# schematic.net
KiCad netlist of a schematic drawn in EAGLE
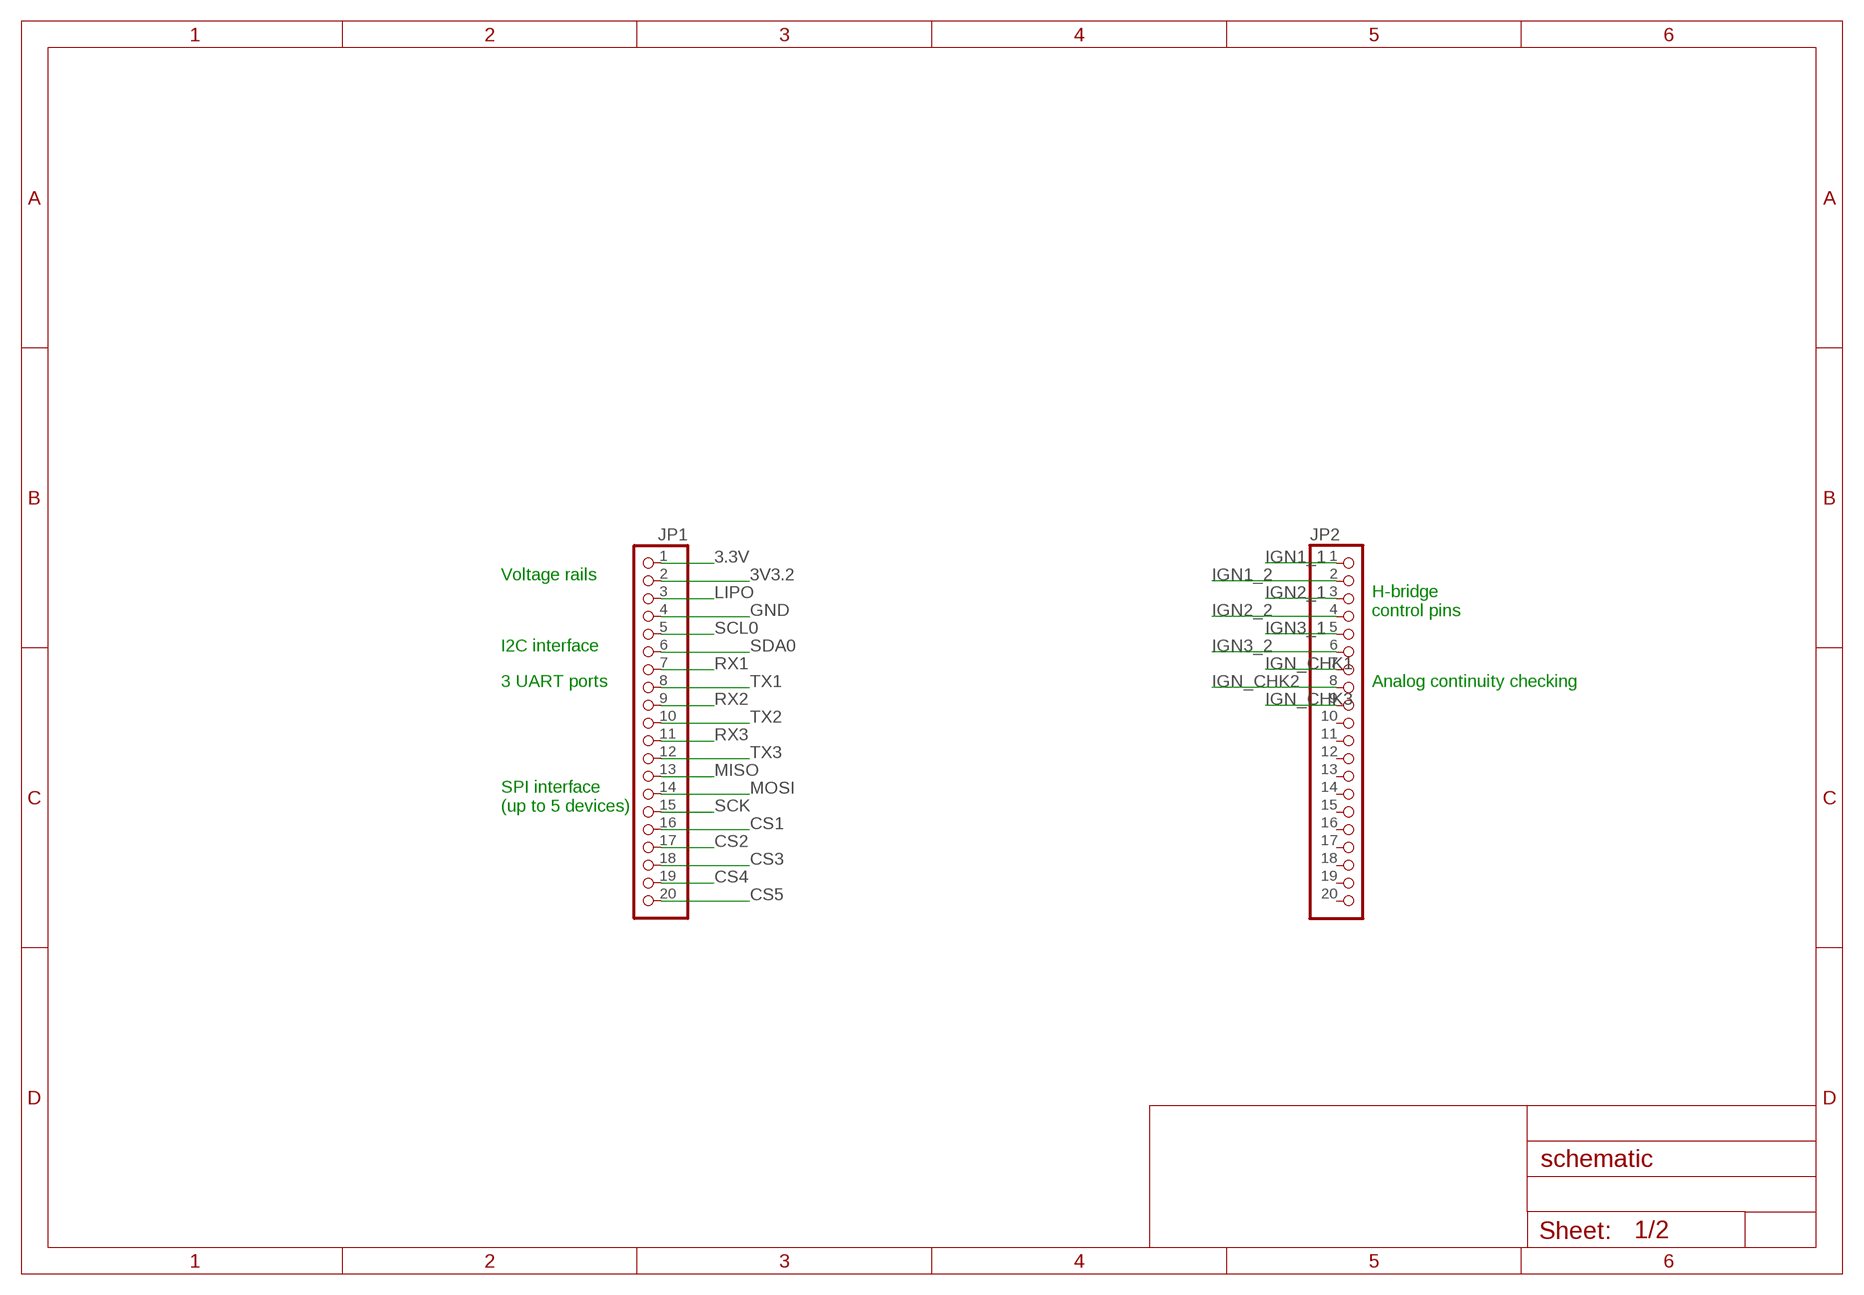
[diagram p0: schematic, sheet 1]
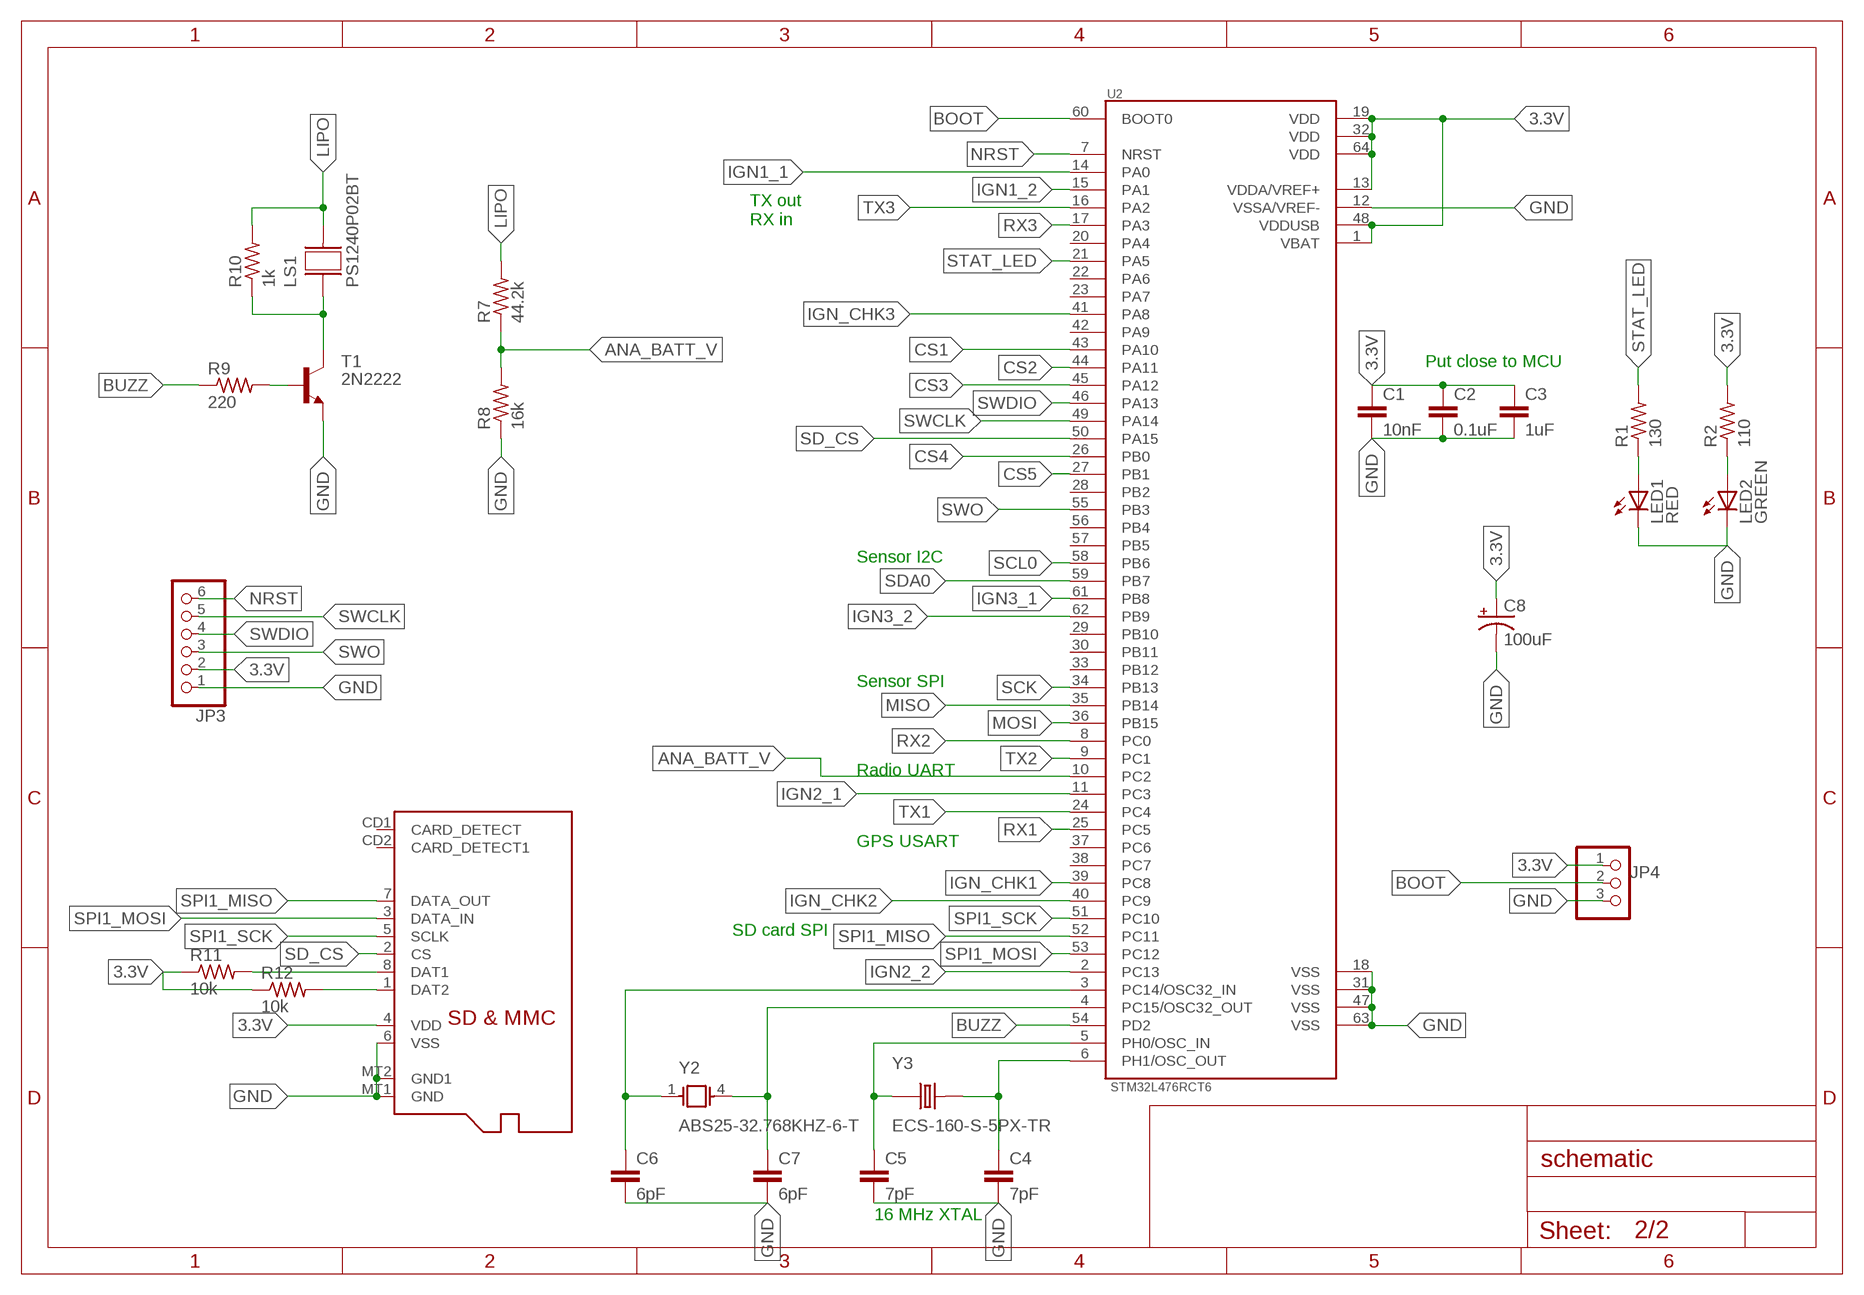
[diagram p1: schematic, sheet 2]

(export (version "E")
  (design (tool "Eeschema 10.0.6"))
  (components
    (comp (ref "JP1")
      (value "PINHD-1X20")
      (footprint "eagle-import:1X20")
      (libsource (lib "eagle-import") (part "PINHD-1X20"))
    )
    (comp (ref "JP2")
      (value "PINHD-1X20")
      (footprint "eagle-import:1X20")
      (libsource (lib "eagle-import") (part "PINHD-1X20"))
    )
    (comp (ref "C1")
      (value "10nF")
      (footprint "eagle-import:C0805")
      (libsource (lib "eagle-import") (part "C-EUC0805"))
    )
    (comp (ref "C2")
      (value "0.1uF")
      (footprint "eagle-import:C0805")
      (libsource (lib "eagle-import") (part "C-EUC0805"))
    )
    (comp (ref "C3")
      (value "1uF")
      (footprint "eagle-import:C0805")
      (libsource (lib "eagle-import") (part "C-EUC0805"))
    )
    (comp (ref "C4")
      (value "7pF")
      (footprint "eagle-import:C0805")
      (libsource (lib "eagle-import") (part "C-EUC0805"))
    )
    (comp (ref "C5")
      (value "7pF")
      (footprint "eagle-import:C0805")
      (libsource (lib "eagle-import") (part "C-EUC0805"))
    )
    (comp (ref "C6")
      (value "6pF")
      (footprint "eagle-import:C0805")
      (libsource (lib "eagle-import") (part "C-EUC0805"))
    )
    (comp (ref "C7")
      (value "6pF")
      (footprint "eagle-import:C0805")
      (libsource (lib "eagle-import") (part "C-EUC0805"))
    )
    (comp (ref "C8")
      (value "100uF")
      (footprint "eagle-import:B45181B")
      (libsource (lib "eagle-import") (part "CPOL-USB45181B"))
    )
    (comp (ref "JP3")
      (value "PINHD-1X6")
      (footprint "eagle-import:1X06")
      (libsource (lib "eagle-import") (part "PINHD-1X6"))
    )
    (comp (ref "JP4")
      (value "PINHD-1X3")
      (footprint "eagle-import:1X03")
      (libsource (lib "eagle-import") (part "PINHD-1X3"))
    )
    (comp (ref "LED1")
      (value "RED")
      (footprint "eagle-import:CHIPLED_0805")
      (libsource (lib "eagle-import") (part "LEDCHIPLED_0805"))
    )
    (comp (ref "LED2")
      (value "GREEN")
      (footprint "eagle-import:CHIPLED_0805")
      (libsource (lib "eagle-import") (part "LEDCHIPLED_0805"))
    )
    (comp (ref "LS1")
      (value "PS1240P02BT")
      (footprint "eagle-import:XDCR_PS1240P02BT")
      (fields (field (name "MF") "TDK"))
      (libsource (lib "eagle-import") (part "PS1240P02BT"))
    )
    (comp (ref "R1")
      (value "130")
      (footprint "eagle-import:R0805")
      (libsource (lib "eagle-import") (part "R-US_R0805"))
    )
    (comp (ref "R2")
      (value "110")
      (footprint "eagle-import:R0805")
      (libsource (lib "eagle-import") (part "R-US_R0805"))
    )
    (comp (ref "R7")
      (value "44.2k")
      (footprint "eagle-import:R0805")
      (libsource (lib "eagle-import") (part "R-US_R0805"))
    )
    (comp (ref "R8")
      (value "16k")
      (footprint "eagle-import:R0805")
      (libsource (lib "eagle-import") (part "R-US_R0805"))
    )
    (comp (ref "R9")
      (value "220")
      (footprint "eagle-import:R0805")
      (libsource (lib "eagle-import") (part "R-US_R0805"))
    )
    (comp (ref "R10")
      (value "1k")
      (footprint "eagle-import:R0805")
      (libsource (lib "eagle-import") (part "R-US_R0805"))
    )
    (comp (ref "R11")
      (value "10k")
      (footprint "eagle-import:R0805")
      (libsource (lib "eagle-import") (part "R-US_R0805"))
    )
    (comp (ref "R12")
      (value "10k")
      (footprint "eagle-import:R0805")
      (libsource (lib "eagle-import") (part "R-US_R0805"))
    )
    (comp (ref "T1")
      (value "2N2222")
      (footprint "eagle-import:TO92-EBC-OVAL")
      (libsource (lib "eagle-import") (part "2N2222"))
    )
    (comp (ref "U$1")
      (value "MICROSD")
      (footprint "eagle-import:MICROSD")
      (libsource (lib "eagle-import") (part "MICROSD"))
    )
    (comp (ref "U2")
      (value "STM32L476RCT6")
      (footprint "eagle-import:QFP50P120X120X160-64N")
      (fields (field (name "MF") "STMicroelectronics"))
      (libsource (lib "eagle-import") (part "STM32L476RCT6"))
    )
    (comp (ref "Y2")
      (value "ABS25-32.768KHZ-6-T")
      (footprint "eagle-import:XTAL_ABS25-32.768KHZ-6-T")
      (fields (field (name "MF") "Abracon"))
      (libsource (lib "eagle-import") (part "ABS25-32.768KHZ-6-T"))
    )
    (comp (ref "Y3")
      (value "ECS-160-S-5PX-TR")
      (footprint "eagle-import:XTAL_ECS-160-S-5PX-TR")
      (fields (field (name "MF") "ECS Inc."))
      (libsource (lib "eagle-import") (part "ECS-160-S-5PX-TR"))
    )
  )
  (nets
    (net (code "1") (name "3.3V") (class "Default")
      (node (ref "C1") (pin "1") (pinfunction "1_1") (pintype "passive"))
      (node (ref "C2") (pin "1") (pinfunction "1_1") (pintype "passive"))
      (node (ref "C3") (pin "1") (pinfunction "1_1") (pintype "passive"))
      (node (ref "C8") (pin "+") (pinfunction "+_+") (pintype "passive"))
      (node (ref "JP1") (pin "1") (pinfunction "1_1") (pintype "passive"))
      (node (ref "JP3") (pin "2") (pinfunction "2_2") (pintype "passive"))
      (node (ref "JP4") (pin "1") (pinfunction "1_1") (pintype "passive"))
      (node (ref "R11") (pin "1") (pinfunction "1_1") (pintype "passive"))
      (node (ref "R12") (pin "1") (pinfunction "1_1") (pintype "passive"))
      (node (ref "R2") (pin "2") (pinfunction "2_2") (pintype "passive"))
      (node (ref "U$1") (pin "4") (pinfunction "VDD_4") (pintype "power_in"))
      (node (ref "U2") (pin "1") (pinfunction "VBAT_1") (pintype "power_in"))
      (node (ref "U2") (pin "13") (pinfunction "VDDA/VREF+_13") (pintype "power_in"))
      (node (ref "U2") (pin "19") (pinfunction "VDD_19") (pintype "power_in"))
      (node (ref "U2") (pin "32") (pinfunction "VDD_32") (pintype "power_in"))
      (node (ref "U2") (pin "48") (pinfunction "VDDUSB_48") (pintype "power_in"))
      (node (ref "U2") (pin "64") (pinfunction "VDD_64") (pintype "power_in"))
    )
    (net (code "2") (name "3V3.2") (class "Default")
      (node (ref "JP1") (pin "2") (pinfunction "2_2") (pintype "passive"))
    )
    (net (code "3") (name "ANA_BATT_V") (class "Default")
      (node (ref "R7") (pin "1") (pinfunction "1_1") (pintype "passive"))
      (node (ref "R8") (pin "2") (pinfunction "2_2") (pintype "passive"))
      (node (ref "U2") (pin "10") (pinfunction "PC2_10") (pintype "bidirectional"))
    )
    (net (code "4") (name "BOOT") (class "Default")
      (node (ref "JP4") (pin "2") (pinfunction "2_2") (pintype "passive"))
      (node (ref "U2") (pin "60") (pinfunction "BOOT0_60") (pintype "input"))
    )
    (net (code "5") (name "BUZZ") (class "Default")
      (node (ref "R9") (pin "1") (pinfunction "1_1") (pintype "passive"))
      (node (ref "U2") (pin "54") (pinfunction "PD2_54") (pintype "bidirectional"))
    )
    (net (code "6") (name "CS1") (class "Default")
      (node (ref "JP1") (pin "16") (pinfunction "16_16") (pintype "passive"))
      (node (ref "U2") (pin "43") (pinfunction "PA10_43") (pintype "bidirectional"))
    )
    (net (code "7") (name "CS2") (class "Default")
      (node (ref "JP1") (pin "17") (pinfunction "17_17") (pintype "passive"))
      (node (ref "U2") (pin "44") (pinfunction "PA11_44") (pintype "bidirectional"))
    )
    (net (code "8") (name "CS3") (class "Default")
      (node (ref "JP1") (pin "18") (pinfunction "18_18") (pintype "passive"))
      (node (ref "U2") (pin "45") (pinfunction "PA12_45") (pintype "bidirectional"))
    )
    (net (code "9") (name "CS4") (class "Default")
      (node (ref "JP1") (pin "19") (pinfunction "19_19") (pintype "passive"))
      (node (ref "U2") (pin "26") (pinfunction "PB0_26") (pintype "bidirectional"))
    )
    (net (code "10") (name "CS5") (class "Default")
      (node (ref "JP1") (pin "20") (pinfunction "20_20") (pintype "passive"))
      (node (ref "U2") (pin "27") (pinfunction "PB1_27") (pintype "bidirectional"))
    )
    (net (code "11") (name "GND") (class "Default")
      (node (ref "C1") (pin "2") (pinfunction "2_2") (pintype "passive"))
      (node (ref "C2") (pin "2") (pinfunction "2_2") (pintype "passive"))
      (node (ref "C3") (pin "2") (pinfunction "2_2") (pintype "passive"))
      (node (ref "C4") (pin "2") (pinfunction "2_2") (pintype "passive"))
      (node (ref "C5") (pin "2") (pinfunction "2_2") (pintype "passive"))
      (node (ref "C6") (pin "2") (pinfunction "2_2") (pintype "passive"))
      (node (ref "C7") (pin "2") (pinfunction "2_2") (pintype "passive"))
      (node (ref "C8") (pin "-") (pinfunction "-_-") (pintype "passive"))
      (node (ref "JP1") (pin "4") (pinfunction "4_4") (pintype "passive"))
      (node (ref "JP3") (pin "1") (pinfunction "1_1") (pintype "passive"))
      (node (ref "JP4") (pin "3") (pinfunction "3_3") (pintype "passive"))
      (node (ref "LED1") (pin "C") (pinfunction "C_C") (pintype "passive"))
      (node (ref "LED2") (pin "C") (pinfunction "C_C") (pintype "passive"))
      (node (ref "R8") (pin "1") (pinfunction "1_1") (pintype "passive"))
      (node (ref "T1") (pin "E") (pinfunction "E_E") (pintype "passive"))
      (node (ref "U$1") (pin "6") (pinfunction "VSS_6") (pintype "power_in"))
      (node (ref "U$1") (pin "MT1") (pinfunction "GND_MT1") (pintype "power_in"))
      (node (ref "U$1") (pin "MT2") (pinfunction "GND1_MT2") (pintype "power_in"))
      (node (ref "U2") (pin "12") (pinfunction "VSSA/VREF-_12") (pintype "power_in"))
      (node (ref "U2") (pin "18") (pinfunction "VSS_18") (pintype "power_in"))
      (node (ref "U2") (pin "31") (pinfunction "VSS_31") (pintype "power_in"))
      (node (ref "U2") (pin "47") (pinfunction "VSS_47") (pintype "power_in"))
      (node (ref "U2") (pin "63") (pinfunction "VSS_63") (pintype "power_in"))
    )
    (net (code "12") (name "IGN1_1") (class "Default")
      (node (ref "JP2") (pin "1") (pinfunction "1_1") (pintype "passive"))
      (node (ref "U2") (pin "14") (pinfunction "PA0_14") (pintype "bidirectional"))
    )
    (net (code "13") (name "IGN1_2") (class "Default")
      (node (ref "JP2") (pin "2") (pinfunction "2_2") (pintype "passive"))
      (node (ref "U2") (pin "15") (pinfunction "PA1_15") (pintype "bidirectional"))
    )
    (net (code "14") (name "IGN2_1") (class "Default")
      (node (ref "JP2") (pin "3") (pinfunction "3_3") (pintype "passive"))
      (node (ref "U2") (pin "11") (pinfunction "PC3_11") (pintype "bidirectional"))
    )
    (net (code "15") (name "IGN2_2") (class "Default")
      (node (ref "JP2") (pin "4") (pinfunction "4_4") (pintype "passive"))
      (node (ref "U2") (pin "2") (pinfunction "PC13_2") (pintype "bidirectional"))
    )
    (net (code "16") (name "IGN3_1") (class "Default")
      (node (ref "JP2") (pin "5") (pinfunction "5_5") (pintype "passive"))
      (node (ref "U2") (pin "61") (pinfunction "PB8_61") (pintype "bidirectional"))
    )
    (net (code "17") (name "IGN3_2") (class "Default")
      (node (ref "JP2") (pin "6") (pinfunction "6_6") (pintype "passive"))
      (node (ref "U2") (pin "62") (pinfunction "PB9_62") (pintype "bidirectional"))
    )
    (net (code "18") (name "IGN_CHK1") (class "Default")
      (node (ref "JP2") (pin "7") (pinfunction "7_7") (pintype "passive"))
      (node (ref "U2") (pin "39") (pinfunction "PC8_39") (pintype "bidirectional"))
    )
    (net (code "19") (name "IGN_CHK2") (class "Default")
      (node (ref "JP2") (pin "8") (pinfunction "8_8") (pintype "passive"))
      (node (ref "U2") (pin "40") (pinfunction "PC9_40") (pintype "bidirectional"))
    )
    (net (code "20") (name "IGN_CHK3") (class "Default")
      (node (ref "JP2") (pin "9") (pinfunction "9_9") (pintype "passive"))
      (node (ref "U2") (pin "41") (pinfunction "PA8_41") (pintype "bidirectional"))
    )
    (net (code "21") (name "LIPO") (class "Default")
      (node (ref "JP1") (pin "3") (pinfunction "3_3") (pintype "passive"))
      (node (ref "LS1") (pin "2") (pinfunction "2_2") (pintype "passive"))
      (node (ref "R10") (pin "2") (pinfunction "2_2") (pintype "passive"))
      (node (ref "R7") (pin "2") (pinfunction "2_2") (pintype "passive"))
    )
    (net (code "22") (name "MISO") (class "Default")
      (node (ref "JP1") (pin "13") (pinfunction "13_13") (pintype "passive"))
      (node (ref "U2") (pin "35") (pinfunction "PB14_35") (pintype "bidirectional"))
    )
    (net (code "23") (name "MOSI") (class "Default")
      (node (ref "JP1") (pin "14") (pinfunction "14_14") (pintype "passive"))
      (node (ref "U2") (pin "36") (pinfunction "PB15_36") (pintype "bidirectional"))
    )
    (net (code "24") (name "NRST") (class "Default")
      (node (ref "JP3") (pin "6") (pinfunction "6_6") (pintype "passive"))
      (node (ref "U2") (pin "7") (pinfunction "NRST_7") (pintype "bidirectional"))
    )
    (net (code "25") (name "Net-(LED1-PadA)") (class "Default")
      (node (ref "LED1") (pin "A") (pinfunction "A_A") (pintype "passive"))
      (node (ref "R1") (pin "1") (pinfunction "1_1") (pintype "passive"))
    )
    (net (code "26") (name "Net-(LED2-PadA)") (class "Default")
      (node (ref "LED2") (pin "A") (pinfunction "A_A") (pintype "passive"))
      (node (ref "R2") (pin "1") (pinfunction "1_1") (pintype "passive"))
    )
    (net (code "27") (name "Net-(LS1-Pad1)") (class "Default")
      (node (ref "LS1") (pin "1") (pinfunction "1_1") (pintype "passive"))
      (node (ref "R10") (pin "1") (pinfunction "1_1") (pintype "passive"))
      (node (ref "T1") (pin "C") (pinfunction "C_C") (pintype "passive"))
    )
    (net (code "28") (name "Net-(R9-Pad2)") (class "Default")
      (node (ref "R9") (pin "2") (pinfunction "2_2") (pintype "passive"))
      (node (ref "T1") (pin "B") (pinfunction "B_B") (pintype "passive"))
    )
    (net (code "29") (name "Net-(U$1-DAT1)") (class "Default")
      (node (ref "R11") (pin "2") (pinfunction "2_2") (pintype "passive"))
      (node (ref "U$1") (pin "8") (pinfunction "DAT1_8") (pintype "bidirectional"))
    )
    (net (code "30") (name "Net-(U$1-DAT2)") (class "Default")
      (node (ref "R12") (pin "2") (pinfunction "2_2") (pintype "passive"))
      (node (ref "U$1") (pin "1") (pinfunction "DAT2_1") (pintype "bidirectional"))
    )
    (net (code "31") (name "Net-(U2-PC14{slash}OSC32_IN)") (class "Default")
      (node (ref "C6") (pin "1") (pinfunction "1_1") (pintype "passive"))
      (node (ref "U2") (pin "3") (pinfunction "PC14/OSC32_IN_3") (pintype "bidirectional"))
      (node (ref "Y2") (pin "1") (pinfunction "1_1") (pintype "passive"))
    )
    (net (code "32") (name "Net-(U2-PC15{slash}OSC32_OUT)") (class "Default")
      (node (ref "C7") (pin "1") (pinfunction "1_1") (pintype "passive"))
      (node (ref "U2") (pin "4") (pinfunction "PC15/OSC32_OUT_4") (pintype "bidirectional"))
      (node (ref "Y2") (pin "4") (pinfunction "4_4") (pintype "passive"))
    )
    (net (code "33") (name "Net-(U2-PH0{slash}OSC_IN)") (class "Default")
      (node (ref "C5") (pin "1") (pinfunction "1_1") (pintype "passive"))
      (node (ref "U2") (pin "5") (pinfunction "PH0/OSC_IN_5") (pintype "bidirectional"))
      (node (ref "Y3") (pin "1") (pinfunction "1_1") (pintype "passive"))
    )
    (net (code "34") (name "Net-(U2-PH1{slash}OSC_OUT)") (class "Default")
      (node (ref "C4") (pin "1") (pinfunction "1_1") (pintype "passive"))
      (node (ref "U2") (pin "6") (pinfunction "PH1/OSC_OUT_6") (pintype "bidirectional"))
      (node (ref "Y3") (pin "2") (pinfunction "2_2") (pintype "passive"))
    )
    (net (code "35") (name "RX1") (class "Default")
      (node (ref "JP1") (pin "7") (pinfunction "7_7") (pintype "passive"))
      (node (ref "U2") (pin "25") (pinfunction "PC5_25") (pintype "bidirectional"))
    )
    (net (code "36") (name "RX2") (class "Default")
      (node (ref "JP1") (pin "9") (pinfunction "9_9") (pintype "passive"))
      (node (ref "U2") (pin "8") (pinfunction "PC0_8") (pintype "bidirectional"))
    )
    (net (code "37") (name "RX3") (class "Default")
      (node (ref "JP1") (pin "11") (pinfunction "11_11") (pintype "passive"))
      (node (ref "U2") (pin "17") (pinfunction "PA3_17") (pintype "bidirectional"))
    )
    (net (code "38") (name "SCK") (class "Default")
      (node (ref "JP1") (pin "15") (pinfunction "15_15") (pintype "passive"))
      (node (ref "U2") (pin "34") (pinfunction "PB13_34") (pintype "bidirectional"))
    )
    (net (code "39") (name "SCL0") (class "Default")
      (node (ref "JP1") (pin "5") (pinfunction "5_5") (pintype "passive"))
      (node (ref "U2") (pin "58") (pinfunction "PB6_58") (pintype "bidirectional"))
    )
    (net (code "40") (name "SDA0") (class "Default")
      (node (ref "JP1") (pin "6") (pinfunction "6_6") (pintype "passive"))
      (node (ref "U2") (pin "59") (pinfunction "PB7_59") (pintype "bidirectional"))
    )
    (net (code "41") (name "SD_CS") (class "Default")
      (node (ref "U$1") (pin "2") (pinfunction "CS_2") (pintype "input"))
      (node (ref "U2") (pin "50") (pinfunction "PA15_50") (pintype "bidirectional"))
    )
    (net (code "42") (name "SPI1_MISO") (class "Default")
      (node (ref "U$1") (pin "7") (pinfunction "DATA_OUT_7") (pintype "output"))
      (node (ref "U2") (pin "52") (pinfunction "PC11_52") (pintype "bidirectional"))
    )
    (net (code "43") (name "SPI1_MOSI") (class "Default")
      (node (ref "U$1") (pin "3") (pinfunction "DATA_IN_3") (pintype "input"))
      (node (ref "U2") (pin "53") (pinfunction "PC12_53") (pintype "bidirectional"))
    )
    (net (code "44") (name "SPI1_SCK") (class "Default")
      (node (ref "U$1") (pin "5") (pinfunction "SCLK_5") (pintype "input"))
      (node (ref "U2") (pin "51") (pinfunction "PC10_51") (pintype "bidirectional"))
    )
    (net (code "45") (name "STAT_LED") (class "Default")
      (node (ref "R1") (pin "2") (pinfunction "2_2") (pintype "passive"))
      (node (ref "U2") (pin "21") (pinfunction "PA5_21") (pintype "bidirectional"))
    )
    (net (code "46") (name "SWCLK") (class "Default")
      (node (ref "JP3") (pin "5") (pinfunction "5_5") (pintype "passive"))
      (node (ref "U2") (pin "49") (pinfunction "PA14_49") (pintype "bidirectional"))
    )
    (net (code "47") (name "SWDIO") (class "Default")
      (node (ref "JP3") (pin "4") (pinfunction "4_4") (pintype "passive"))
      (node (ref "U2") (pin "46") (pinfunction "PA13_46") (pintype "bidirectional"))
    )
    (net (code "48") (name "SWO") (class "Default")
      (node (ref "JP3") (pin "3") (pinfunction "3_3") (pintype "passive"))
      (node (ref "U2") (pin "55") (pinfunction "PB3_55") (pintype "bidirectional"))
    )
    (net (code "49") (name "TX1") (class "Default")
      (node (ref "JP1") (pin "8") (pinfunction "8_8") (pintype "passive"))
      (node (ref "U2") (pin "24") (pinfunction "PC4_24") (pintype "bidirectional"))
    )
    (net (code "50") (name "TX2") (class "Default")
      (node (ref "JP1") (pin "10") (pinfunction "10_10") (pintype "passive"))
      (node (ref "U2") (pin "9") (pinfunction "PC1_9") (pintype "bidirectional"))
    )
    (net (code "51") (name "TX3") (class "Default")
      (node (ref "JP1") (pin "12") (pinfunction "12_12") (pintype "passive"))
      (node (ref "U2") (pin "16") (pinfunction "PA2_16") (pintype "bidirectional"))
    )
    (net (code "52") (name "unconnected-(JP2-Pad10)") (class "Default")
      (node (ref "JP2") (pin "10") (pinfunction "10_10") (pintype "passive"))
    )
    (net (code "53") (name "unconnected-(JP2-Pad11)") (class "Default")
      (node (ref "JP2") (pin "11") (pinfunction "11_11") (pintype "passive"))
    )
    (net (code "54") (name "unconnected-(JP2-Pad12)") (class "Default")
      (node (ref "JP2") (pin "12") (pinfunction "12_12") (pintype "passive"))
    )
    (net (code "55") (name "unconnected-(JP2-Pad13)") (class "Default")
      (node (ref "JP2") (pin "13") (pinfunction "13_13") (pintype "passive"))
    )
    (net (code "56") (name "unconnected-(JP2-Pad14)") (class "Default")
      (node (ref "JP2") (pin "14") (pinfunction "14_14") (pintype "passive"))
    )
    (net (code "57") (name "unconnected-(JP2-Pad15)") (class "Default")
      (node (ref "JP2") (pin "15") (pinfunction "15_15") (pintype "passive"))
    )
    (net (code "58") (name "unconnected-(JP2-Pad16)") (class "Default")
      (node (ref "JP2") (pin "16") (pinfunction "16_16") (pintype "passive"))
    )
    (net (code "59") (name "unconnected-(JP2-Pad17)") (class "Default")
      (node (ref "JP2") (pin "17") (pinfunction "17_17") (pintype "passive"))
    )
    (net (code "60") (name "unconnected-(JP2-Pad18)") (class "Default")
      (node (ref "JP2") (pin "18") (pinfunction "18_18") (pintype "passive"))
    )
    (net (code "61") (name "unconnected-(JP2-Pad19)") (class "Default")
      (node (ref "JP2") (pin "19") (pinfunction "19_19") (pintype "passive"))
    )
    (net (code "62") (name "unconnected-(JP2-Pad20)") (class "Default")
      (node (ref "JP2") (pin "20") (pinfunction "20_20") (pintype "passive"))
    )
    (net (code "63") (name "unconnected-(U$1-CARD_DETECT-PadCD1)") (class "Default")
      (node (ref "U$1") (pin "CD1") (pinfunction "CARD_DETECT_CD1") (pintype "passive"))
    )
    (net (code "64") (name "unconnected-(U$1-CARD_DETECT1-PadCD2)") (class "Default")
      (node (ref "U$1") (pin "CD2") (pinfunction "CARD_DETECT1_CD2") (pintype "passive"))
    )
    (net (code "65") (name "unconnected-(U2-PA4-Pad20)") (class "Default")
      (node (ref "U2") (pin "20") (pinfunction "PA4_20") (pintype "bidirectional"))
    )
    (net (code "66") (name "unconnected-(U2-PA6-Pad22)") (class "Default")
      (node (ref "U2") (pin "22") (pinfunction "PA6_22") (pintype "bidirectional"))
    )
    (net (code "67") (name "unconnected-(U2-PA7-Pad23)") (class "Default")
      (node (ref "U2") (pin "23") (pinfunction "PA7_23") (pintype "bidirectional"))
    )
    (net (code "68") (name "unconnected-(U2-PA9-Pad42)") (class "Default")
      (node (ref "U2") (pin "42") (pinfunction "PA9_42") (pintype "bidirectional"))
    )
    (net (code "69") (name "unconnected-(U2-PB2-Pad28)") (class "Default")
      (node (ref "U2") (pin "28") (pinfunction "PB2_28") (pintype "bidirectional"))
    )
    (net (code "70") (name "unconnected-(U2-PB4-Pad56)") (class "Default")
      (node (ref "U2") (pin "56") (pinfunction "PB4_56") (pintype "bidirectional"))
    )
    (net (code "71") (name "unconnected-(U2-PB5-Pad57)") (class "Default")
      (node (ref "U2") (pin "57") (pinfunction "PB5_57") (pintype "bidirectional"))
    )
    (net (code "72") (name "unconnected-(U2-PB10-Pad29)") (class "Default")
      (node (ref "U2") (pin "29") (pinfunction "PB10_29") (pintype "bidirectional"))
    )
    (net (code "73") (name "unconnected-(U2-PB11-Pad30)") (class "Default")
      (node (ref "U2") (pin "30") (pinfunction "PB11_30") (pintype "bidirectional"))
    )
    (net (code "74") (name "unconnected-(U2-PB12-Pad33)") (class "Default")
      (node (ref "U2") (pin "33") (pinfunction "PB12_33") (pintype "bidirectional"))
    )
    (net (code "75") (name "unconnected-(U2-PC6-Pad37)") (class "Default")
      (node (ref "U2") (pin "37") (pinfunction "PC6_37") (pintype "bidirectional"))
    )
    (net (code "76") (name "unconnected-(U2-PC7-Pad38)") (class "Default")
      (node (ref "U2") (pin "38") (pinfunction "PC7_38") (pintype "bidirectional"))
    )
  )
)
